# PowerStack.net
KiCad netlist of a schematic drawn in EasyEDA Pro
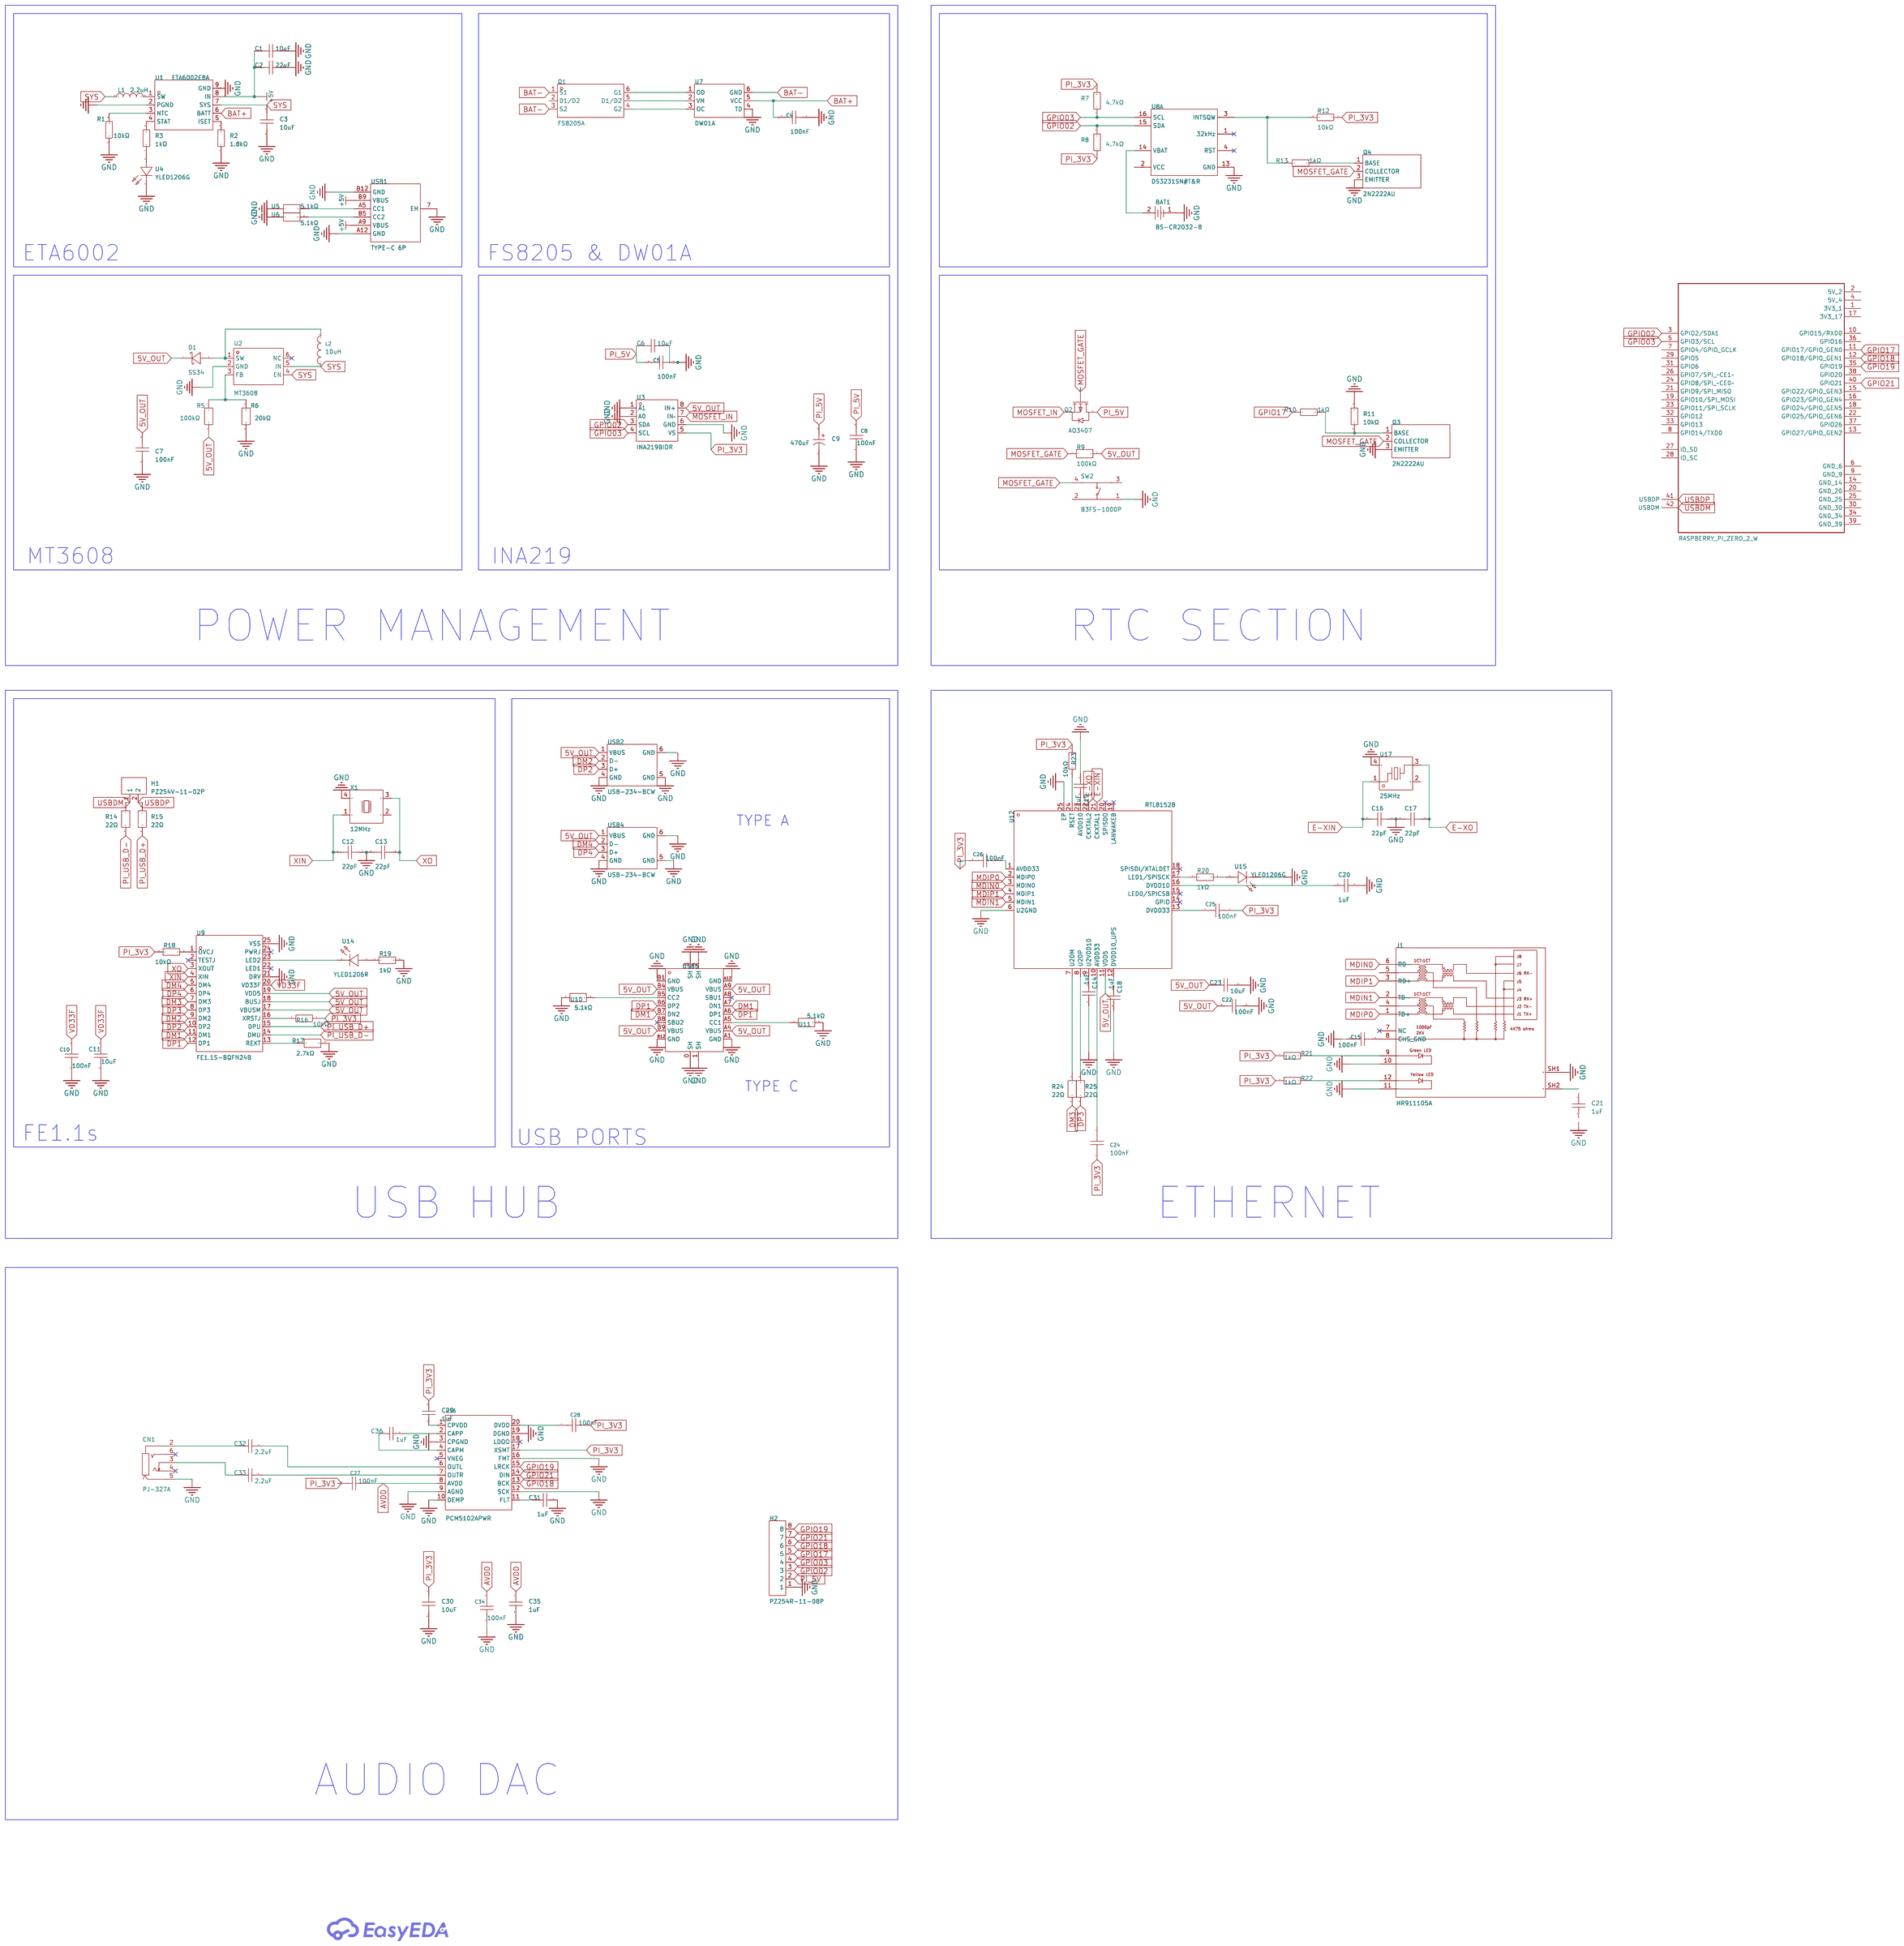
[diagram p0: schematic sheet]

(export (version "E")
  (design (tool "Eeschema 10.0.6"))
  (components
    (comp (ref "BAT1")
      (value "BS-CR2032-8")
      (footprint "easyedapro:BAT-SMD_BS-CR2032-8")
      (fields (field (name "Manufacturer") "LX(连欣科技)"))
      (libsource (lib "easyedapro") (part "BS-CR2032-8"))
    )
    (comp (ref "C1")
      (value "10uF")
      (footprint "easyedapro:C0603")
      (description "Capacitance:10uF Tolerance:±10% Tolerance:±10% Voltage Rating:10V Temperature Coefficient:X5R")
      (fields
        (field (name "Manufacturer Part") "CL10A106KP8NNNC")
        (field (name "Manufacturer") "SAMSUNG(三星)")
      )
      (libsource (lib "easyedapro") (part "CL10A106KP8NNNC"))
    )
    (comp (ref "C2")
      (value "22uF")
      (footprint "easyedapro:C0603")
      (description "Capacitance:22uF Tolerance:±20% Tolerance:±20% Voltage Rating:10V Temperature Coefficient:X5R")
      (fields
        (field (name "Manufacturer Part") "CL10A226MP8NUNE")
        (field (name "Manufacturer") "SAMSUNG(三星)")
      )
      (libsource (lib "easyedapro") (part "CL10A226MP8NUNE"))
    )
    (comp (ref "C3")
      (value "10uF")
      (footprint "easyedapro:C0603")
      (description "Capacitance:10uF Tolerance:±10% Tolerance:±10% Voltage Rating:10V Temperature Coefficient:X5R")
      (fields
        (field (name "Manufacturer Part") "CL10A106KP8NNNC")
        (field (name "Manufacturer") "SAMSUNG(三星)")
      )
      (libsource (lib "easyedapro") (part "CL10A106KP8NNNC"))
    )
    (comp (ref "C4")
      (value "100nF")
      (footprint "easyedapro:C0603")
      (description "Capacitance:100nF Tolerance:±10% Tolerance:±10% Voltage Rating:50V Temperature Coefficient:X7R")
      (fields
        (field (name "Manufacturer Part") "CC0603KRX7R9BB104")
        (field (name "Manufacturer") "YAGEO(国巨)")
      )
      (libsource (lib "easyedapro") (part "CC0603KRX7R9BB104"))
    )
    (comp (ref "C5")
      (value "100nF")
      (footprint "easyedapro:C0603")
      (description "Capacitance:100nF Tolerance:±10% Tolerance:±10% Voltage Rating:50V Temperature Coefficient:X7R")
      (fields
        (field (name "Manufacturer Part") "CC0603KRX7R9BB104")
        (field (name "Manufacturer") "YAGEO(国巨)")
      )
      (libsource (lib "easyedapro") (part "CC0603KRX7R9BB104"))
    )
    (comp (ref "C6")
      (value "10uF")
      (footprint "easyedapro:C0603")
      (description "Capacitance:10uF Tolerance:±10% Tolerance:±10% Voltage Rating:10V Temperature Coefficient:X5R")
      (fields
        (field (name "Manufacturer Part") "CL10A106KP8NNNC")
        (field (name "Manufacturer") "SAMSUNG(三星)")
      )
      (libsource (lib "easyedapro") (part "CL10A106KP8NNNC"))
    )
    (comp (ref "C7")
      (value "100nF")
      (footprint "easyedapro:C0603")
      (description "Capacitance:100nF Tolerance:±10% Tolerance:±10% Voltage Rating:50V Temperature Coefficient:X7R")
      (fields
        (field (name "Manufacturer Part") "CC0603KRX7R9BB104")
        (field (name "Manufacturer") "YAGEO(国巨)")
      )
      (libsource (lib "easyedapro") (part "CC0603KRX7R9BB104"))
    )
    (comp (ref "C8")
      (value "100nF")
      (footprint "easyedapro:C0603")
      (description "Capacitance:100nF Tolerance:±10% Tolerance:±10% Voltage Rating:50V Temperature Coefficient:X7R")
      (fields
        (field (name "Manufacturer Part") "CC0603KRX7R9BB104")
        (field (name "Manufacturer") "YAGEO(国巨)")
      )
      (libsource (lib "easyedapro") (part "CC0603KRX7R9BB104"))
    )
    (comp (ref "C9")
      (value "470uF")
      (footprint "easyedapro:CAP-SMD_BD6.3-L6.6-W6.6-FD")
      (fields (field (name "Manufacturer Part") "126RV0010") (field (name "Manufacturer") "KNSCHA(科尼盛)"))
      (libsource (lib "easyedapro") (part "126RV0010"))
    )
    (comp (ref "C10")
      (value "100nF")
      (footprint "easyedapro:C0603")
      (description "Capacitance:100nF Tolerance:±10% Tolerance:±10% Voltage Rating:50V Temperature Coefficient:X7R")
      (fields
        (field (name "Manufacturer Part") "CC0603KRX7R9BB104")
        (field (name "Manufacturer") "YAGEO(国巨)")
      )
      (libsource (lib "easyedapro") (part "CC0603KRX7R9BB104"))
    )
    (comp (ref "C11")
      (value "10uF")
      (footprint "easyedapro:C0603")
      (description "Capacitance:10uF Tolerance:±10% Tolerance:±10% Voltage Rating:10V Temperature Coefficient:X5R")
      (fields
        (field (name "Manufacturer Part") "CL10A106KP8NNNC")
        (field (name "Manufacturer") "SAMSUNG(三星)")
      )
      (libsource (lib "easyedapro") (part "CL10A106KP8NNNC"))
    )
    (comp (ref "C12")
      (value "22pF")
      (footprint "easyedapro:C0805")
      (description "Capacitance:22pF Tolerance:±5% Tolerance:±5% Voltage Rating:50V Temperature Coefficient:C0G")
      (fields
        (field (name "Manufacturer Part") "TCC0805COG220J500BT")
        (field (name "Manufacturer") "CCTC(三环)")
      )
      (libsource (lib "easyedapro") (part "TCC0805COG220J500BT"))
    )
    (comp (ref "C13")
      (value "22pF")
      (footprint "easyedapro:C0805")
      (description "Capacitance:22pF Tolerance:±5% Tolerance:±5% Voltage Rating:50V Temperature Coefficient:C0G")
      (fields
        (field (name "Manufacturer Part") "TCC0805COG220J500BT")
        (field (name "Manufacturer") "CCTC(三环)")
      )
      (libsource (lib "easyedapro") (part "TCC0805COG220J500BT"))
    )
    (comp (ref "C14")
      (value "1uF")
      (footprint "easyedapro:C0603")
      (description "Capacitance:1uF Tolerance:±10% Tolerance:±10% Voltage Rating:25V Temperature Coefficient:X7R")
      (fields
        (field (name "Manufacturer Part") "CL10B105KA8NNNC")
        (field (name "Manufacturer") "SAMSUNG(三星)")
      )
      (libsource (lib "easyedapro") (part "CL10B105KA8NNNC"))
    )
    (comp (ref "C15")
      (value "100nF")
      (footprint "easyedapro:C0603")
      (description "Capacitance:100nF Tolerance:±10% Tolerance:±10% Voltage Rating:50V Temperature Coefficient:X7R")
      (fields
        (field (name "Manufacturer Part") "CC0603KRX7R9BB104")
        (field (name "Manufacturer") "YAGEO(国巨)")
      )
      (libsource (lib "easyedapro") (part "CC0603KRX7R9BB104"))
    )
    (comp (ref "C16")
      (value "22pF")
      (footprint "easyedapro:C0805")
      (description "Capacitance:22pF Tolerance:±5% Tolerance:±5% Voltage Rating:50V Temperature Coefficient:C0G")
      (fields
        (field (name "Manufacturer Part") "TCC0805COG220J500BT")
        (field (name "Manufacturer") "CCTC(三环)")
      )
      (libsource (lib "easyedapro") (part "TCC0805COG220J500BT"))
    )
    (comp (ref "C17")
      (value "22pF")
      (footprint "easyedapro:C0805")
      (description "Capacitance:22pF Tolerance:±5% Tolerance:±5% Voltage Rating:50V Temperature Coefficient:C0G")
      (fields
        (field (name "Manufacturer Part") "TCC0805COG220J500BT")
        (field (name "Manufacturer") "CCTC(三环)")
      )
      (libsource (lib "easyedapro") (part "TCC0805COG220J500BT"))
    )
    (comp (ref "C18")
      (value "1uF")
      (footprint "easyedapro:C0603")
      (description "Capacitance:1uF Tolerance:±10% Tolerance:±10% Voltage Rating:25V Temperature Coefficient:X7R")
      (fields
        (field (name "Manufacturer Part") "CL10B105KA8NNNC")
        (field (name "Manufacturer") "SAMSUNG(三星)")
      )
      (libsource (lib "easyedapro") (part "CL10B105KA8NNNC"))
    )
    (comp (ref "C19")
      (value "1uF")
      (footprint "easyedapro:C0603")
      (description "Capacitance:1uF Tolerance:±10% Tolerance:±10% Voltage Rating:25V Temperature Coefficient:X7R")
      (fields
        (field (name "Manufacturer Part") "CL10B105KA8NNNC")
        (field (name "Manufacturer") "SAMSUNG(三星)")
      )
      (libsource (lib "easyedapro") (part "CL10B105KA8NNNC"))
    )
    (comp (ref "C20")
      (value "1uF")
      (footprint "easyedapro:C0603")
      (description "Capacitance:1uF Tolerance:±10% Tolerance:±10% Voltage Rating:25V Temperature Coefficient:X7R")
      (fields
        (field (name "Manufacturer Part") "CL10B105KA8NNNC")
        (field (name "Manufacturer") "SAMSUNG(三星)")
      )
      (libsource (lib "easyedapro") (part "CL10B105KA8NNNC"))
    )
    (comp (ref "C21")
      (value "1uF")
      (footprint "easyedapro:C0603")
      (description "Capacitance:1uF Tolerance:±10% Tolerance:±10% Voltage Rating:25V Temperature Coefficient:X7R")
      (fields
        (field (name "Manufacturer Part") "CL10B105KA8NNNC")
        (field (name "Manufacturer") "SAMSUNG(三星)")
      )
      (libsource (lib "easyedapro") (part "CL10B105KA8NNNC"))
    )
    (comp (ref "C22")
      (value "100nF")
      (footprint "easyedapro:C0603")
      (description "Capacitance:100nF Tolerance:±10% Tolerance:±10% Voltage Rating:50V Temperature Coefficient:X7R")
      (fields
        (field (name "Manufacturer Part") "CC0603KRX7R9BB104")
        (field (name "Manufacturer") "YAGEO(国巨)")
      )
      (libsource (lib "easyedapro") (part "CC0603KRX7R9BB104"))
    )
    (comp (ref "C23")
      (value "10uF")
      (footprint "easyedapro:C0603")
      (description "Capacitance:10uF Tolerance:±10% Tolerance:±10% Voltage Rating:10V Temperature Coefficient:X5R")
      (fields
        (field (name "Manufacturer Part") "CL10A106KP8NNNC")
        (field (name "Manufacturer") "SAMSUNG(三星)")
      )
      (libsource (lib "easyedapro") (part "CL10A106KP8NNNC"))
    )
    (comp (ref "C24")
      (value "100nF")
      (footprint "easyedapro:C0603")
      (description "Capacitance:100nF Tolerance:±10% Tolerance:±10% Voltage Rating:50V Temperature Coefficient:X7R")
      (fields
        (field (name "Manufacturer Part") "CC0603KRX7R9BB104")
        (field (name "Manufacturer") "YAGEO(国巨)")
      )
      (libsource (lib "easyedapro") (part "CC0603KRX7R9BB104"))
    )
    (comp (ref "C25")
      (value "100nF")
      (footprint "easyedapro:C0603")
      (description "Capacitance:100nF Tolerance:±10% Tolerance:±10% Voltage Rating:50V Temperature Coefficient:X7R")
      (fields
        (field (name "Manufacturer Part") "CC0603KRX7R9BB104")
        (field (name "Manufacturer") "YAGEO(国巨)")
      )
      (libsource (lib "easyedapro") (part "CC0603KRX7R9BB104"))
    )
    (comp (ref "C26")
      (value "100nF")
      (footprint "easyedapro:C0603")
      (description "Capacitance:100nF Tolerance:±10% Tolerance:±10% Voltage Rating:50V Temperature Coefficient:X7R")
      (fields
        (field (name "Manufacturer Part") "CC0603KRX7R9BB104")
        (field (name "Manufacturer") "YAGEO(国巨)")
      )
      (libsource (lib "easyedapro") (part "CC0603KRX7R9BB104"))
    )
    (comp (ref "C27")
      (value "100nF")
      (footprint "easyedapro:C0603")
      (description "Capacitance:100nF Tolerance:±10% Tolerance:±10% Voltage Rating:50V Temperature Coefficient:X7R")
      (fields
        (field (name "Manufacturer Part") "CC0603KRX7R9BB104")
        (field (name "Manufacturer") "YAGEO(国巨)")
      )
      (libsource (lib "easyedapro") (part "CC0603KRX7R9BB104"))
    )
    (comp (ref "C28")
      (value "100nF")
      (footprint "easyedapro:C0603")
      (description "Capacitance:100nF Tolerance:±10% Tolerance:±10% Voltage Rating:50V Temperature Coefficient:X7R")
      (fields
        (field (name "Manufacturer Part") "CC0603KRX7R9BB104")
        (field (name "Manufacturer") "YAGEO(国巨)")
      )
      (libsource (lib "easyedapro") (part "CC0603KRX7R9BB104"))
    )
    (comp (ref "C29")
      (value "1uF")
      (footprint "easyedapro:C0603")
      (description "Capacitance:1uF Tolerance:±10% Tolerance:±10% Voltage Rating:25V Temperature Coefficient:X7R")
      (fields
        (field (name "Manufacturer Part") "CL10B105KA8NNNC")
        (field (name "Manufacturer") "SAMSUNG(三星)")
      )
      (libsource (lib "easyedapro") (part "CL10B105KA8NNNC"))
    )
    (comp (ref "C30")
      (value "10uF")
      (footprint "easyedapro:C0603")
      (description "Capacitance:10uF Tolerance:±10% Tolerance:±10% Voltage Rating:10V Temperature Coefficient:X5R")
      (fields
        (field (name "Manufacturer Part") "CL10A106KP8NNNC")
        (field (name "Manufacturer") "SAMSUNG(三星)")
      )
      (libsource (lib "easyedapro") (part "CL10A106KP8NNNC"))
    )
    (comp (ref "C31")
      (value "1uF")
      (footprint "easyedapro:C0603")
      (description "Capacitance:1uF Tolerance:±10% Tolerance:±10% Voltage Rating:25V Temperature Coefficient:X7R")
      (fields
        (field (name "Manufacturer Part") "CL10B105KA8NNNC")
        (field (name "Manufacturer") "SAMSUNG(三星)")
      )
      (libsource (lib "easyedapro") (part "CL10B105KA8NNNC"))
    )
    (comp (ref "C32")
      (value "2.2uF")
      (footprint "easyedapro:C0603")
      (description "Capacitance:2.2uF Tolerance:±10% Tolerance:±10% Voltage Rating:16V Temperature Coefficient:X5R")
      (fields
        (field (name "Manufacturer Part") "CL10A225KO8NNNC")
        (field (name "Manufacturer") "SAMSUNG(三星)")
      )
      (libsource (lib "easyedapro") (part "CL10A225KO8NNNC"))
    )
    (comp (ref "C33")
      (value "2.2uF")
      (footprint "easyedapro:C0603")
      (description "Capacitance:2.2uF Tolerance:±10% Tolerance:±10% Voltage Rating:16V Temperature Coefficient:X5R")
      (fields
        (field (name "Manufacturer Part") "CL10A225KO8NNNC")
        (field (name "Manufacturer") "SAMSUNG(三星)")
      )
      (libsource (lib "easyedapro") (part "CL10A225KO8NNNC"))
    )
    (comp (ref "C34")
      (value "100nF")
      (footprint "easyedapro:C0603")
      (description "Capacitance:100nF Tolerance:±10% Tolerance:±10% Voltage Rating:50V Temperature Coefficient:X7R")
      (fields
        (field (name "Manufacturer Part") "CC0603KRX7R9BB104")
        (field (name "Manufacturer") "YAGEO(国巨)")
      )
      (libsource (lib "easyedapro") (part "CC0603KRX7R9BB104"))
    )
    (comp (ref "C35")
      (value "1uF")
      (footprint "easyedapro:C0603")
      (description "Capacitance:1uF Tolerance:±10% Tolerance:±10% Voltage Rating:25V Temperature Coefficient:X7R")
      (fields
        (field (name "Manufacturer Part") "CL10B105KA8NNNC")
        (field (name "Manufacturer") "SAMSUNG(三星)")
      )
      (libsource (lib "easyedapro") (part "CL10B105KA8NNNC"))
    )
    (comp (ref "C36")
      (value "1uF")
      (footprint "easyedapro:C0603")
      (description "Capacitance:1uF Tolerance:±10% Tolerance:±10% Voltage Rating:25V Temperature Coefficient:X7R")
      (fields
        (field (name "Manufacturer Part") "CL10B105KA8NNNC")
        (field (name "Manufacturer") "SAMSUNG(三星)")
      )
      (libsource (lib "easyedapro") (part "CL10B105KA8NNNC"))
    )
    (comp (ref "CN1")
      (value "PJ-327A")
      (footprint "easyedapro:AUDIO-SMD_XUNPU_PJ-327A")
      (fields (field (name "Manufacturer") "XUNPU(讯普)"))
      (libsource (lib "easyedapro") (part "PJ-327A"))
    )
    (comp (ref "D1")
      (value "SS34")
      (footprint "easyedapro:SMA_L4.3-W2.6-LS5.1-RD")
      (fields (field (name "Manufacturer") "Hangyu(航昱微)"))
      (libsource (lib "easyedapro") (part "SS34_C52023881"))
    )
    (comp (ref "H1")
      (value "PZ254V-11-02P")
      (footprint "easyedapro:HDR-TH_2P-P2.54-V-M")
      (fields (field (name "Manufacturer") "XFCN(兴飞)"))
      (libsource (lib "easyedapro") (part "PZ254V-11-02P"))
    )
    (comp (ref "H2")
      (value "PZ254R-11-08P")
      (footprint "easyedapro:HDR-TH_8P-P2.54-H-M-W10.4")
      (fields (field (name "Manufacturer") "XFCN(兴飞)"))
      (libsource (lib "easyedapro") (part "PZ254R-11-08P"))
    )
    (comp (ref "J1")
      (value "HR911105A")
      (footprint "easyedapro:RJ45-TH_HR911105A")
      (fields (field (name "Manufacturer") "HANRUN(汉仁)"))
      (libsource (lib "easyedapro") (part "HR911105A_C12074"))
    )
    (comp (ref "L1")
      (value "2.2uH")
      (footprint "easyedapro:IND-SMD_L5.4-W5.2")
      (fields (field (name "Manufacturer Part") "APH0530T2R2M") (field (name "Manufacturer") "APV(爱普微)"))
      (libsource (lib "easyedapro") (part "APH0530T2R2M"))
    )
    (comp (ref "L2")
      (value "10uH")
      (footprint "easyedapro:IND-SMD_L5.2-W5.2_MCW-0530")
      (fields (field (name "Manufacturer Part") "SMMS0530-100M") (field (name "Manufacturer") "SXN(顺翔诺)"))
      (libsource (lib "easyedapro") (part "SMMS0530-100M"))
    )
    (comp (ref "Q1")
      (value "FS8205A")
      (footprint "easyedapro:SOT-23-6_L2.9-W1.6-P0.95-LS2.8-BR")
      (fields (field (name "Manufacturer") "TECH PUBLIC(台舟)"))
      (libsource (lib "easyedapro") (part "FS8205A_C2830320"))
    )
    (comp (ref "Q2")
      (value "AO3407")
      (footprint "easyedapro:SOT-23-3_L2.9-W1.6-P1.90-LS2.8-BR")
      (fields (field (name "Manufacturer") "YONGYUTAI(永裕泰)"))
      (libsource (lib "easyedapro") (part "AO3407_C54839874"))
    )
    (comp (ref "Q3")
      (value "2N2222AU")
      (footprint "easyedapro:SOT-89-3_L4.5-W2.4-P1.50-LS4.0-BR")
      (fields (field (name "Manufacturer") "CBI(创基)"))
      (libsource (lib "easyedapro") (part "2N2222AU"))
    )
    (comp (ref "Q4")
      (value "2N2222AU")
      (footprint "easyedapro:SOT-89-3_L4.5-W2.4-P1.50-LS4.0-BR")
      (fields (field (name "Manufacturer") "CBI(创基)"))
      (libsource (lib "easyedapro") (part "2N2222AU"))
    )
    (comp (ref "R1")
      (value "10kΩ")
      (footprint "easyedapro:R0603")
      (fields (field (name "Manufacturer Part") "RC0603FR-0710KL") (field (name "Manufacturer") "YAGEO(国巨)"))
      (libsource (lib "easyedapro") (part "RC0603FR-0710KL"))
    )
    (comp (ref "R2")
      (value "1.8kΩ")
      (footprint "easyedapro:R0603")
      (fields (field (name "Manufacturer Part") "RC0603FR-071K8L") (field (name "Manufacturer") "YAGEO(国巨)"))
      (libsource (lib "easyedapro") (part "RC0603FR-071K8L"))
    )
    (comp (ref "R3")
      (value "1kΩ")
      (footprint "easyedapro:R0603")
      (fields (field (name "Manufacturer Part") "RC0603FR-071KL") (field (name "Manufacturer") "YAGEO(国巨)"))
      (libsource (lib "easyedapro") (part "RC0603FR-071KL"))
    )
    (comp (ref "R5")
      (value "100kΩ")
      (footprint "easyedapro:R0603")
      (fields (field (name "Manufacturer Part") "FRC0603F1003TS") (field (name "Manufacturer") "FOJAN(富捷)"))
      (libsource (lib "easyedapro") (part "FRC0603F1003TS"))
    )
    (comp (ref "R6")
      (value "20kΩ")
      (footprint "easyedapro:R0603")
      (fields (field (name "Manufacturer Part") "FRC0603F2002TS") (field (name "Manufacturer") "FOJAN(富捷)"))
      (libsource (lib "easyedapro") (part "FRC0603F2002TS"))
    )
    (comp (ref "R7")
      (value "4.7kΩ")
      (footprint "easyedapro:R0603")
      (fields (field (name "Manufacturer Part") "RC0603FR-074K7L") (field (name "Manufacturer") "YAGEO(国巨)"))
      (libsource (lib "easyedapro") (part "RC0603FR-074K7L"))
    )
    (comp (ref "R8")
      (value "4.7kΩ")
      (footprint "easyedapro:R0603")
      (fields (field (name "Manufacturer Part") "RC0603FR-074K7L") (field (name "Manufacturer") "YAGEO(国巨)"))
      (libsource (lib "easyedapro") (part "RC0603FR-074K7L"))
    )
    (comp (ref "R9")
      (value "100kΩ")
      (footprint "easyedapro:R0603")
      (fields (field (name "Manufacturer Part") "FRC0603F1003TS") (field (name "Manufacturer") "FOJAN(富捷)"))
      (libsource (lib "easyedapro") (part "FRC0603F1003TS"))
    )
    (comp (ref "R10")
      (value "1kΩ")
      (footprint "easyedapro:R0603")
      (fields (field (name "Manufacturer Part") "RC0603FR-071KL") (field (name "Manufacturer") "YAGEO(国巨)"))
      (libsource (lib "easyedapro") (part "RC0603FR-071KL"))
    )
    (comp (ref "R11")
      (value "10kΩ")
      (footprint "easyedapro:R0603")
      (fields (field (name "Manufacturer Part") "RC0603FR-0710KL") (field (name "Manufacturer") "YAGEO(国巨)"))
      (libsource (lib "easyedapro") (part "RC0603FR-0710KL"))
    )
    (comp (ref "R12")
      (value "10kΩ")
      (footprint "easyedapro:R0603")
      (fields (field (name "Manufacturer Part") "RC0603FR-0710KL") (field (name "Manufacturer") "YAGEO(国巨)"))
      (libsource (lib "easyedapro") (part "RC0603FR-0710KL"))
    )
    (comp (ref "R13")
      (value "1kΩ")
      (footprint "easyedapro:R0603")
      (fields (field (name "Manufacturer Part") "RC0603FR-071KL") (field (name "Manufacturer") "YAGEO(国巨)"))
      (libsource (lib "easyedapro") (part "RC0603FR-071KL"))
    )
    (comp (ref "R14")
      (value "22Ω")
      (footprint "easyedapro:R0603")
      (fields (field (name "Manufacturer Part") "FRC0603F22R0TS") (field (name "Manufacturer") "FOJAN(富捷)"))
      (libsource (lib "easyedapro") (part "FRC0603F22R0TS"))
    )
    (comp (ref "R15")
      (value "22Ω")
      (footprint "easyedapro:R0603")
      (fields (field (name "Manufacturer Part") "FRC0603F22R0TS") (field (name "Manufacturer") "FOJAN(富捷)"))
      (libsource (lib "easyedapro") (part "FRC0603F22R0TS"))
    )
    (comp (ref "R16")
      (value "10kΩ")
      (footprint "easyedapro:R0603")
      (fields (field (name "Manufacturer Part") "RC0603FR-0710KL") (field (name "Manufacturer") "YAGEO(国巨)"))
      (libsource (lib "easyedapro") (part "RC0603FR-0710KL"))
    )
    (comp (ref "R17")
      (value "2.7kΩ")
      (footprint "easyedapro:R0603")
      (fields (field (name "Manufacturer Part") "FRC0603F2701TS") (field (name "Manufacturer") "FOJAN(富捷)"))
      (libsource (lib "easyedapro") (part "FRC0603F2701TS"))
    )
    (comp (ref "R18")
      (value "10kΩ")
      (footprint "easyedapro:R0603")
      (fields (field (name "Manufacturer Part") "RC0603FR-0710KL") (field (name "Manufacturer") "YAGEO(国巨)"))
      (libsource (lib "easyedapro") (part "RC0603FR-0710KL"))
    )
    (comp (ref "R19")
      (value "1kΩ")
      (footprint "easyedapro:R0603")
      (fields (field (name "Manufacturer Part") "RC0603FR-071KL") (field (name "Manufacturer") "YAGEO(国巨)"))
      (libsource (lib "easyedapro") (part "RC0603FR-071KL"))
    )
    (comp (ref "R20")
      (value "1kΩ")
      (footprint "easyedapro:R0603")
      (fields (field (name "Manufacturer Part") "RC0603FR-071KL") (field (name "Manufacturer") "YAGEO(国巨)"))
      (libsource (lib "easyedapro") (part "RC0603FR-071KL"))
    )
    (comp (ref "R21")
      (value "1kΩ")
      (footprint "easyedapro:R0603")
      (fields (field (name "Manufacturer Part") "RC0603FR-071KL") (field (name "Manufacturer") "YAGEO(国巨)"))
      (libsource (lib "easyedapro") (part "RC0603FR-071KL"))
    )
    (comp (ref "R22")
      (value "1kΩ")
      (footprint "easyedapro:R0603")
      (fields (field (name "Manufacturer Part") "RC0603FR-071KL") (field (name "Manufacturer") "YAGEO(国巨)"))
      (libsource (lib "easyedapro") (part "RC0603FR-071KL"))
    )
    (comp (ref "R23")
      (value "10kΩ")
      (footprint "easyedapro:R0603")
      (fields (field (name "Manufacturer Part") "RC0603FR-0710KL") (field (name "Manufacturer") "YAGEO(国巨)"))
      (libsource (lib "easyedapro") (part "RC0603FR-0710KL"))
    )
    (comp (ref "R24")
      (value "22Ω")
      (footprint "easyedapro:R0603")
      (fields (field (name "Manufacturer Part") "FRC0603F22R0TS") (field (name "Manufacturer") "FOJAN(富捷)"))
      (libsource (lib "easyedapro") (part "FRC0603F22R0TS"))
    )
    (comp (ref "R25")
      (value "22Ω")
      (footprint "easyedapro:R0603")
      (fields (field (name "Manufacturer Part") "FRC0603F22R0TS") (field (name "Manufacturer") "FOJAN(富捷)"))
      (libsource (lib "easyedapro") (part "FRC0603F22R0TS"))
    )
    (comp (ref "SW2")
      (value "B3FS-1000P")
      (footprint "easyedapro:KEY-SMD_4P-L6.0-W6.3-P4.50-LS8.0")
      (fields (field (name "Manufacturer") "OMRON(欧姆龙)"))
      (libsource (lib "easyedapro") (part "B3FS-1000P"))
    )
    (comp (ref "U1")
      (value "ETA6002E8A")
      (footprint "easyedapro:ESOP-8_L4.9-W3.9-P1.27-LS6.0-BL-EP-1")
      (fields (field (name "Manufacturer") "ETA(钰泰)"))
      (libsource (lib "easyedapro") (part "ETA6002E8A"))
    )
    (comp (ref "U2")
      (value "MT3608")
      (footprint "easyedapro:SOT-23-6_L2.9-W1.6-P0.95-LS2.8-BL")
      (fields (field (name "Manufacturer") "西安航天民芯"))
      (libsource (lib "easyedapro") (part "MT3608"))
    )
    (comp (ref "U3")
      (value "INA219BIDR")
      (footprint "easyedapro:SOIC-8_L5.0-W4.0-P1.27-LS6.1-BL")
      (fields (field (name "Manufacturer") "TI(德州仪器)"))
      (libsource (lib "easyedapro") (part "INA219BIDR"))
    )
    (comp (ref "U4")
      (value "YLED1206G")
      (footprint "easyedapro:LED1206-RD")
      (fields (field (name "Manufacturer") "YONGYUTAI(永裕泰)"))
      (libsource (lib "easyedapro") (part "YLED1206G"))
    )
    (comp (ref "U5")
      (value "5.1kΩ")
      (footprint "easyedapro:R0603")
      (fields (field (name "Manufacturer Part") "FRC0603F5101TS") (field (name "Manufacturer") "FOJAN(富捷)"))
      (libsource (lib "easyedapro") (part "FRC0603F5101TS"))
    )
    (comp (ref "U6")
      (value "5.1kΩ")
      (footprint "easyedapro:R0603")
      (fields (field (name "Manufacturer Part") "FRC0603F5101TS") (field (name "Manufacturer") "FOJAN(富捷)"))
      (libsource (lib "easyedapro") (part "FRC0603F5101TS"))
    )
    (comp (ref "U7")
      (value "DW01A")
      (footprint "easyedapro:SOT-23-6_L2.9-W1.6-P0.95-LS2.8-BL")
      (fields (field (name "Manufacturer") "PUOLOP(迪浦)"))
      (libsource (lib "easyedapro") (part "DW01A_C351410"))
    )
    (comp (ref "U8")
      (value "DS3231SN#T&R")
      (footprint "easyedapro:SOIC-16_L10.3-W7.5-P1.27-LS10.3-BL")
      (fields (field (name "Manufacturer") "ADI(亚德诺)/MAXIM(美信)"))
      (libsource (lib "easyedapro") (part "DS3231SN#"))
    )
    (comp (ref "U9")
      (value "FE1.1S-BQFN24B")
      (footprint "easyedapro:WQFN-24_L4.0-W4.0-P0.50-TL-EP2.7")
      (fields (field (name "Manufacturer") "TERMINUS"))
      (libsource (lib "easyedapro") (part "FE1.1S-BQFN24B"))
    )
    (comp (ref "U10")
      (value "5.1kΩ")
      (footprint "easyedapro:R0603")
      (fields (field (name "Manufacturer Part") "FRC0603F5101TS") (field (name "Manufacturer") "FOJAN(富捷)"))
      (libsource (lib "easyedapro") (part "FRC0603F5101TS"))
    )
    (comp (ref "U11")
      (value "5.1kΩ")
      (footprint "easyedapro:R0603")
      (fields (field (name "Manufacturer Part") "FRC0603F5101TS") (field (name "Manufacturer") "FOJAN(富捷)"))
      (libsource (lib "easyedapro") (part "FRC0603F5101TS"))
    )
    (comp (ref "U12")
      (value "RTL8152B")
      (footprint "easyedapro:QFN-24_L4.0-W4.0-P0.50-BL-EP2.0")
      (fields (field (name "Manufacturer") "REALTEK(瑞昱)"))
      (libsource (lib "easyedapro") (part "RTL8152B-VB-CG"))
    )
    (comp (ref "U14")
      (value "YLED1206R")
      (footprint "easyedapro:LED1206-FD")
      (fields (field (name "Manufacturer") "YONGYUTAI(永裕泰)"))
      (libsource (lib "easyedapro") (part "YLED1206R"))
    )
    (comp (ref "U15")
      (value "YLED1206G")
      (footprint "easyedapro:LED1206-RD")
      (fields (field (name "Manufacturer") "YONGYUTAI(永裕泰)"))
      (libsource (lib "easyedapro") (part "YLED1206G"))
    )
    (comp (ref "U16")
      (value "PCM5102APWR")
      (footprint "easyedapro:TSSOP-20_L6.5-W4.4-P0.65-LS6.4-BL")
      (fields (field (name "Manufacturer") "TI(德州仪器)"))
      (libsource (lib "easyedapro") (part "PCM5102APWR"))
    )
    (comp (ref "U17")
      (value "25MHz")
      (footprint "easyedapro:CRYSTAL-SMD_4P-L2.0-W1.6-BL")
      (fields
        (field (name "Manufacturer Part") "XL7EL89CKI-111YLC-25M")
        (field (name "Manufacturer") "YXC(扬兴晶振)")
      )
      (libsource (lib "easyedapro") (part "XL7EL89CKI-111YLC-25M"))
    )
    (comp (ref "U18")
      (value "RASPBERRY_PI_ZERO_2_W")
      (footprint "easyedapro:MODULE_RASPBERRY_PI_ZERO_2_W")
      (libsource (lib "easyedapro") (part "RASPBERRY_PI_ZERO_2_W"))
    )
    (comp (ref "USB1")
      (value "TYPE-C 6P")
      (footprint "easyedapro:TYPE-C-SMD_TYPE-C-6P_1")
      (fields (field (name "Manufacturer") "SHOU HAN(首韩)"))
      (libsource (lib "easyedapro") (part "TYPE-C 6P"))
    )
    (comp (ref "USB2")
      (value "USB-234-BCW")
      (footprint "easyedapro:USB-A-SMD_USB-234-BCW")
      (fields (field (name "Manufacturer") "XUNPU(讯普)"))
      (libsource (lib "easyedapro") (part "USB-234-BCW"))
    )
    (comp (ref "USB4")
      (value "USB-234-BCW")
      (footprint "easyedapro:USB-A-SMD_USB-234-BCW")
      (fields (field (name "Manufacturer") "XUNPU(讯普)"))
      (libsource (lib "easyedapro") (part "USB-234-BCW"))
    )
    (comp (ref "USB5")
      (value "TYPE C")
      (footprint "easyedapro:USB-C_SMD-TYPE-C-31-M-12")
      (fields (field (name "Manufacturer") "DEALON(德艺隆)"))
      (libsource (lib "easyedapro") (part "USB-TYPE-C-018"))
    )
    (comp (ref "X1")
      (value "12MHz")
      (footprint "easyedapro:OSC-SMD_4P-L5.0-W3.2-BL_SG5032")
      (fields
        (field (name "Manufacturer Part") "OVETGLJANF-12MHZ")
        (field (name "Manufacturer") "TAITIEN(泰艺电子)")
      )
      (libsource (lib "easyedapro") (part "OVETGLJANF-12MHZ"))
    )
  )
  (nets
    (net (code "1") (name "+5V") (class "Default")
      (node (ref "C1") (pin "1") (pinfunction "1_1") (pintype "unspecified"))
      (node (ref "C2") (pin "1") (pinfunction "1_1") (pintype "unspecified"))
      (node (ref "U1") (pin "8") (pinfunction "IN_8") (pintype "unspecified"))
      (node (ref "USB1") (pin "A9") (pinfunction "VBUS_A9") (pintype "unspecified"))
      (node (ref "USB1") (pin "B9") (pinfunction "VBUS_B9") (pintype "unspecified"))
    )
    (net (code "2") (name "5V_OUT") (class "Default")
      (node (ref "C22") (pin "2") (pinfunction "2_2") (pintype "unspecified"))
      (node (ref "C23") (pin "1") (pinfunction "1_1") (pintype "unspecified"))
      (node (ref "C7") (pin "2") (pinfunction "2_2") (pintype "unspecified"))
      (node (ref "D1") (pin "1") (pinfunction "C_1") (pintype "unspecified"))
      (node (ref "R5") (pin "2") (pinfunction "2_2") (pintype "unspecified"))
      (node (ref "R9") (pin "2") (pinfunction "2_2") (pintype "unspecified"))
      (node (ref "U12") (pin "11") (pinfunction "VDD5_11") (pintype "unspecified"))
      (node (ref "U3") (pin "8") (pinfunction "IN+_8") (pintype "unspecified"))
      (node (ref "U9") (pin "17") (pinfunction "VBUSM_17") (pintype "unspecified"))
      (node (ref "U9") (pin "18") (pinfunction "BUSJ_18") (pintype "unspecified"))
      (node (ref "U9") (pin "19") (pinfunction "VDD5_19") (pintype "unspecified"))
      (node (ref "USB2") (pin "1") (pinfunction "VBUS_1") (pintype "unspecified"))
      (node (ref "USB4") (pin "1") (pinfunction "VBUS_1") (pintype "unspecified"))
      (node (ref "USB5") (pin "A4") (pinfunction "VBUS_A4") (pintype "unspecified"))
      (node (ref "USB5") (pin "A9") (pinfunction "VBUS_A9") (pintype "unspecified"))
      (node (ref "USB5") (pin "B4") (pinfunction "VBUS_B4") (pintype "unspecified"))
      (node (ref "USB5") (pin "B9") (pinfunction "VBUS_B9") (pintype "unspecified"))
    )
    (net (code "3") (name "AVDD") (class "Default")
      (node (ref "C27") (pin "1") (pinfunction "1_1") (pintype "unspecified"))
      (node (ref "C34") (pin "2") (pinfunction "2_2") (pintype "unspecified"))
      (node (ref "C35") (pin "1") (pinfunction "1_1") (pintype "input"))
      (node (ref "U16") (pin "8") (pinfunction "AVDD_8") (pintype "input"))
    )
    (net (code "4") (name "BAT+") (class "Default")
      (node (ref "C4") (pin "2") (pinfunction "2_2") (pintype "unspecified"))
      (node (ref "U1") (pin "6") (pinfunction "BATT_6") (pintype "unspecified"))
      (node (ref "U7") (pin "5") (pinfunction "VCC_5") (pintype "unspecified"))
    )
    (net (code "5") (name "BAT-") (class "Default")
      (node (ref "Q1") (pin "1") (pinfunction "S1_1") (pintype "unspecified"))
      (node (ref "Q1") (pin "3") (pinfunction "S2_3") (pintype "unspecified"))
      (node (ref "U7") (pin "6") (pinfunction "GND_6") (pintype "unspecified"))
    )
    (net (code "6") (name "DM1") (class "Default")
      (node (ref "U9") (pin "11") (pinfunction "DM1_11") (pintype "unspecified"))
      (node (ref "USB5") (pin "A7") (pinfunction "DN1_A7") (pintype "unspecified"))
      (node (ref "USB5") (pin "B7") (pinfunction "DN2_B7") (pintype "unspecified"))
    )
    (net (code "7") (name "DM2") (class "Default")
      (node (ref "U9") (pin "9") (pinfunction "DM2_9") (pintype "unspecified"))
      (node (ref "USB2") (pin "2") (pinfunction "D-_2") (pintype "unspecified"))
    )
    (net (code "8") (name "DM3") (class "Default")
      (node (ref "R24") (pin "2") (pinfunction "2_2") (pintype "unspecified"))
      (node (ref "U9") (pin "7") (pinfunction "DM3_7") (pintype "unspecified"))
    )
    (net (code "9") (name "DM4") (class "Default")
      (node (ref "U9") (pin "5") (pinfunction "DM4_5") (pintype "unspecified"))
      (node (ref "USB4") (pin "2") (pinfunction "D-_2") (pintype "unspecified"))
    )
    (net (code "10") (name "DP1") (class "Default")
      (node (ref "U9") (pin "12") (pinfunction "DP1_12") (pintype "unspecified"))
      (node (ref "USB5") (pin "A6") (pinfunction "DP1_A6") (pintype "unspecified"))
      (node (ref "USB5") (pin "B6") (pinfunction "DP2_B6") (pintype "unspecified"))
    )
    (net (code "11") (name "DP2") (class "Default")
      (node (ref "U9") (pin "10") (pinfunction "DP2_10") (pintype "unspecified"))
      (node (ref "USB2") (pin "3") (pinfunction "D+_3") (pintype "unspecified"))
    )
    (net (code "12") (name "DP3") (class "Default")
      (node (ref "R25") (pin "2") (pinfunction "2_2") (pintype "unspecified"))
      (node (ref "U9") (pin "8") (pinfunction "DP3_8") (pintype "unspecified"))
    )
    (net (code "13") (name "DP4") (class "Default")
      (node (ref "U9") (pin "6") (pinfunction "DP4_6") (pintype "unspecified"))
      (node (ref "USB4") (pin "3") (pinfunction "D+_3") (pintype "unspecified"))
    )
    (net (code "14") (name "E-XIN") (class "Default")
      (node (ref "C16") (pin "2") (pinfunction "2_2") (pintype "unspecified"))
      (node (ref "U12") (pin "21") (pinfunction "CKXTAL1_21") (pintype "unspecified"))
      (node (ref "U17") (pin "1") (pinfunction "1_1") (pintype "input"))
    )
    (net (code "15") (name "E-XO") (class "Default")
      (node (ref "C17") (pin "2") (pinfunction "2_2") (pintype "unspecified"))
      (node (ref "U12") (pin "22") (pinfunction "CKXTAL2_22") (pintype "unspecified"))
      (node (ref "U17") (pin "3") (pinfunction "3_3") (pintype "input"))
    )
    (net (code "16") (name "GND") (class "Default")
      (node (ref "BAT1") (pin "1") (pinfunction "1_1") (pintype "input"))
      (node (ref "C1") (pin "2") (pinfunction "2_2") (pintype "unspecified"))
      (node (ref "C10") (pin "1") (pinfunction "1_1") (pintype "unspecified"))
      (node (ref "C11") (pin "2") (pinfunction "2_2") (pintype "unspecified"))
      (node (ref "C12") (pin "1") (pinfunction "1_1") (pintype "unspecified"))
      (node (ref "C13") (pin "1") (pinfunction "1_1") (pintype "unspecified"))
      (node (ref "C14") (pin "1") (pinfunction "1_1") (pintype "input"))
      (node (ref "C15") (pin "2") (pinfunction "2_2") (pintype "unspecified"))
      (node (ref "C16") (pin "1") (pinfunction "1_1") (pintype "unspecified"))
      (node (ref "C17") (pin "1") (pinfunction "1_1") (pintype "unspecified"))
      (node (ref "C18") (pin "1") (pinfunction "1_1") (pintype "input"))
      (node (ref "C19") (pin "1") (pinfunction "1_1") (pintype "input"))
      (node (ref "C2") (pin "2") (pinfunction "2_2") (pintype "unspecified"))
      (node (ref "C20") (pin "1") (pinfunction "1_1") (pintype "input"))
      (node (ref "C22") (pin "1") (pinfunction "1_1") (pintype "unspecified"))
      (node (ref "C23") (pin "2") (pinfunction "2_2") (pintype "unspecified"))
      (node (ref "C3") (pin "2") (pinfunction "2_2") (pintype "unspecified"))
      (node (ref "C30") (pin "2") (pinfunction "2_2") (pintype "unspecified"))
      (node (ref "C31") (pin "2") (pinfunction "2_2") (pintype "input"))
      (node (ref "C34") (pin "1") (pinfunction "1_1") (pintype "unspecified"))
      (node (ref "C35") (pin "2") (pinfunction "2_2") (pintype "input"))
      (node (ref "C4") (pin "1") (pinfunction "1_1") (pintype "unspecified"))
      (node (ref "C5") (pin "1") (pinfunction "1_1") (pintype "unspecified"))
      (node (ref "C6") (pin "2") (pinfunction "2_2") (pintype "unspecified"))
      (node (ref "C7") (pin "1") (pinfunction "1_1") (pintype "unspecified"))
      (node (ref "C8") (pin "1") (pinfunction "1_1") (pintype "unspecified"))
      (node (ref "C9") (pin "2") (pinfunction "2_2") (pintype "input"))
      (node (ref "CN1") (pin "5") (pinfunction "5_5") (pintype "unspecified"))
      (node (ref "H2") (pin "1") (pinfunction "1_1") (pintype "unspecified"))
      (node (ref "J1") (pin "10") (pinfunction "10_10") (pintype "unspecified"))
      (node (ref "J1") (pin "11") (pinfunction "11_11") (pintype "unspecified"))
      (node (ref "J1") (pin "SH1") (pinfunction "SH1_SH1") (pintype "unspecified"))
      (node (ref "Q3") (pin "3") (pinfunction "EMITTER_3") (pintype "unspecified"))
      (node (ref "Q4") (pin "3") (pinfunction "EMITTER_3") (pintype "unspecified"))
      (node (ref "R1") (pin "1") (pinfunction "1_1") (pintype "input"))
      (node (ref "R11") (pin "1") (pinfunction "1_1") (pintype "input"))
      (node (ref "R17") (pin "2") (pinfunction "2_2") (pintype "unspecified"))
      (node (ref "R19") (pin "2") (pinfunction "2_2") (pintype "input"))
      (node (ref "R2") (pin "1") (pinfunction "1_1") (pintype "unspecified"))
      (node (ref "R6") (pin "1") (pinfunction "1_1") (pintype "unspecified"))
      (node (ref "SW2") (pin "1") (pinfunction "1_1") (pintype "unspecified"))
      (node (ref "U1") (pin "9") (pinfunction "GND_9") (pintype "unspecified"))
      (node (ref "U10") (pin "1") (pinfunction "1_1") (pintype "unspecified"))
      (node (ref "U11") (pin "2") (pinfunction "2_2") (pintype "unspecified"))
      (node (ref "U12") (pin "25") (pinfunction "EP_25") (pintype "unspecified"))
      (node (ref "U12") (pin "6") (pinfunction "U2GND_6") (pintype "unspecified"))
      (node (ref "U15") (pin "1") (pinfunction "K_1") (pintype "unspecified"))
      (node (ref "U16") (pin "10") (pinfunction "DEMP_10") (pintype "input"))
      (node (ref "U16") (pin "12") (pinfunction "SCK_12") (pintype "input"))
      (node (ref "U16") (pin "16") (pinfunction "FMT_16") (pintype "input"))
      (node (ref "U16") (pin "19") (pinfunction "DGND_19") (pintype "input"))
      (node (ref "U16") (pin "3") (pinfunction "CPGND_3") (pintype "input"))
      (node (ref "U16") (pin "9") (pinfunction "AGND_9") (pintype "input"))
      (node (ref "U17") (pin "4") (pinfunction "GND_4") (pintype "input"))
      (node (ref "U2") (pin "2") (pinfunction "GND_2") (pintype "unspecified"))
      (node (ref "U3") (pin "1") (pinfunction "A1_1") (pintype "unspecified"))
      (node (ref "U3") (pin "2") (pinfunction "A0_2") (pintype "unspecified"))
      (node (ref "U3") (pin "6") (pinfunction "GND_6") (pintype "unspecified"))
      (node (ref "U4") (pin "1") (pinfunction "K_1") (pintype "unspecified"))
      (node (ref "U5") (pin "1") (pinfunction "1_1") (pintype "unspecified"))
      (node (ref "U6") (pin "1") (pinfunction "1_1") (pintype "unspecified"))
      (node (ref "U7") (pin "4") (pinfunction "TD_4") (pintype "unspecified"))
      (node (ref "U8") (pin "13") (pinfunction "GND_13") (pintype "unspecified"))
      (node (ref "U9") (pin "21") (pinfunction "DRV_21") (pintype "unspecified"))
      (node (ref "U9") (pin "25") (pinfunction "VSS_25") (pintype "unspecified"))
      (node (ref "USB1") (pin "7") (pinfunction "EH_7") (pintype "unspecified"))
      (node (ref "USB1") (pin "A12") (pinfunction "GND_A12") (pintype "unspecified"))
      (node (ref "USB1") (pin "B12") (pinfunction "GND_B12") (pintype "unspecified"))
      (node (ref "USB2") (pin "4") (pinfunction "GND_4") (pintype "unspecified"))
      (node (ref "USB2") (pin "5") (pinfunction "GND_5") (pintype "unspecified"))
      (node (ref "USB2") (pin "6") (pinfunction "GND_6") (pintype "unspecified"))
      (node (ref "USB4") (pin "4") (pinfunction "GND_4") (pintype "unspecified"))
      (node (ref "USB4") (pin "5") (pinfunction "GND_5") (pintype "unspecified"))
      (node (ref "USB4") (pin "6") (pinfunction "GND_6") (pintype "unspecified"))
      (node (ref "USB5") (pin "0") (pinfunction "SH_0") (pintype "unspecified"))
      (node (ref "USB5") (pin "1") (pinfunction "SH_1") (pintype "unspecified"))
      (node (ref "USB5") (pin "2") (pinfunction "SH_2") (pintype "unspecified"))
      (node (ref "USB5") (pin "3") (pinfunction "SH_3") (pintype "unspecified"))
      (node (ref "USB5") (pin "A1") (pinfunction "GND_A1") (pintype "unspecified"))
      (node (ref "USB5") (pin "A12") (pinfunction "GND_A12") (pintype "unspecified"))
      (node (ref "USB5") (pin "B1") (pinfunction "GND_B1") (pintype "unspecified"))
      (node (ref "USB5") (pin "B12") (pinfunction "GND_B12") (pintype "unspecified"))
      (node (ref "X1") (pin "4") (pinfunction "VCC_4") (pintype "unspecified"))
    )
    (net (code "17") (name "GPIO02") (class "Default")
      (node (ref "H2") (pin "3") (pinfunction "3_3") (pintype "unspecified"))
      (node (ref "R8") (pin "2") (pinfunction "2_2") (pintype "input"))
      (node (ref "U18") (pin "3") (pinfunction "GPIO2/SDA1_3") (pintype "bidirectional"))
      (node (ref "U3") (pin "3") (pinfunction "SDA_3") (pintype "unspecified"))
      (node (ref "U8") (pin "15") (pinfunction "SDA_15") (pintype "bidirectional"))
    )
    (net (code "18") (name "GPIO03") (class "Default")
      (node (ref "H2") (pin "4") (pinfunction "4_4") (pintype "unspecified"))
      (node (ref "R7") (pin "1") (pinfunction "1_1") (pintype "input"))
      (node (ref "U18") (pin "5") (pinfunction "GPIO3/SCL_5") (pintype "bidirectional"))
      (node (ref "U3") (pin "4") (pinfunction "SCL_4") (pintype "unspecified"))
      (node (ref "U8") (pin "16") (pinfunction "SCL_16") (pintype "unspecified"))
    )
    (net (code "19") (name "GPIO17") (class "Default")
      (node (ref "H2") (pin "5") (pinfunction "5_5") (pintype "unspecified"))
      (node (ref "R10") (pin "1") (pinfunction "1_1") (pintype "input"))
      (node (ref "U18") (pin "11") (pinfunction "GPIO17/GPIO_GEN0_11") (pintype "bidirectional"))
    )
    (net (code "20") (name "GPIO18") (class "Default")
      (node (ref "H2") (pin "6") (pinfunction "6_6") (pintype "unspecified"))
      (node (ref "U16") (pin "13") (pinfunction "BCK_13") (pintype "input"))
      (node (ref "U18") (pin "12") (pinfunction "GPIO18/GPIO_GEN1_12") (pintype "bidirectional"))
    )
    (net (code "21") (name "GPIO19") (class "Default")
      (node (ref "H2") (pin "8") (pinfunction "8_8") (pintype "unspecified"))
      (node (ref "U16") (pin "15") (pinfunction "LRCK_15") (pintype "input"))
      (node (ref "U18") (pin "35") (pinfunction "GPIO19_35") (pintype "bidirectional"))
    )
    (net (code "22") (name "GPIO21") (class "Default")
      (node (ref "H2") (pin "7") (pinfunction "7_7") (pintype "unspecified"))
      (node (ref "U16") (pin "14") (pinfunction "DIN_14") (pintype "input"))
      (node (ref "U18") (pin "40") (pinfunction "GPIO21_40") (pintype "bidirectional"))
    )
    (net (code "23") (name "MDIN0") (class "Default")
      (node (ref "J1") (pin "6") (pinfunction "RD-_6") (pintype "unspecified"))
      (node (ref "U12") (pin "3") (pinfunction "MDIN0_3") (pintype "unspecified"))
    )
    (net (code "24") (name "MDIN1") (class "Default")
      (node (ref "J1") (pin "2") (pinfunction "TD-_2") (pintype "unspecified"))
      (node (ref "U12") (pin "5") (pinfunction "MDIN1_5") (pintype "unspecified"))
    )
    (net (code "25") (name "MDIP0") (class "Default")
      (node (ref "J1") (pin "1") (pinfunction "TD+_1") (pintype "unspecified"))
      (node (ref "U12") (pin "2") (pinfunction "MDIP0_2") (pintype "unspecified"))
    )
    (net (code "26") (name "MDIP1") (class "Default")
      (node (ref "J1") (pin "3") (pinfunction "RD+_3") (pintype "unspecified"))
      (node (ref "U12") (pin "4") (pinfunction "MDIP1_4") (pintype "unspecified"))
    )
    (net (code "27") (name "MOSFET_GATE") (class "Default")
      (node (ref "Q2") (pin "1") (pinfunction "G_1") (pintype "unspecified"))
      (node (ref "Q3") (pin "2") (pinfunction "COLLECTOR_2") (pintype "unspecified"))
      (node (ref "Q4") (pin "2") (pinfunction "COLLECTOR_2") (pintype "unspecified"))
      (node (ref "R9") (pin "1") (pinfunction "1_1") (pintype "unspecified"))
      (node (ref "SW2") (pin "4") (pinfunction "4_4") (pintype "unspecified"))
    )
    (net (code "28") (name "MOSFET_IN") (class "Default")
      (node (ref "Q2") (pin "2") (pinfunction "S_2") (pintype "unspecified"))
      (node (ref "U3") (pin "7") (pinfunction "IN–_7") (pintype "unspecified"))
    )
    (net (code "29") (name "Net-(C24-Pad1)") (class "Default")
      (node (ref "C24") (pin "1") (pinfunction "1_1") (pintype "unspecified"))
      (node (ref "U12") (pin "10") (pinfunction "AVDD33_10") (pintype "unspecified"))
    )
    (net (code "30") (name "Net-(C26-Pad1)") (class "Default")
      (node (ref "C26") (pin "1") (pinfunction "1_1") (pintype "unspecified"))
      (node (ref "U12") (pin "1") (pinfunction "AVDD33_1") (pintype "unspecified"))
    )
    (net (code "31") (name "Net-(C32-Pad1)") (class "Default")
      (node (ref "C32") (pin "1") (pinfunction "1_1") (pintype "input"))
      (node (ref "CN1") (pin "2") (pinfunction "2_2") (pintype "unspecified"))
    )
    (net (code "32") (name "Net-(C33-Pad1)") (class "Default")
      (node (ref "C33") (pin "1") (pinfunction "1_1") (pintype "input"))
      (node (ref "CN1") (pin "3") (pinfunction "3_3") (pintype "unspecified"))
    )
    (net (code "33") (name "Net-(D1-A)") (class "Default")
      (node (ref "D1") (pin "2") (pinfunction "A_2") (pintype "unspecified"))
      (node (ref "L2") (pin "2") (pinfunction "2_2") (pintype "input"))
      (node (ref "U2") (pin "1") (pinfunction "SW_1") (pintype "unspecified"))
    )
    (net (code "34") (name "Net-(J1-CHS_GND)") (class "Default")
      (node (ref "C15") (pin "1") (pinfunction "1_1") (pintype "unspecified"))
      (node (ref "J1") (pin "8") (pinfunction "CHS_GND_8") (pintype "unspecified"))
    )
    (net (code "35") (name "Net-(J1-Pad9)") (class "Default")
      (node (ref "J1") (pin "9") (pinfunction "9_9") (pintype "unspecified"))
      (node (ref "R21") (pin "1") (pinfunction "1_1") (pintype "input"))
    )
    (net (code "36") (name "Net-(J1-Pad12)") (class "Default")
      (node (ref "J1") (pin "12") (pinfunction "12_12") (pintype "unspecified"))
      (node (ref "R22") (pin "1") (pinfunction "1_1") (pintype "input"))
    )
    (net (code "37") (name "Net-(Q1-G1)") (class "Default")
      (node (ref "Q1") (pin "6") (pinfunction "G1_6") (pintype "unspecified"))
      (node (ref "U7") (pin "1") (pinfunction "OD_1") (pintype "unspecified"))
    )
    (net (code "38") (name "Net-(Q1-G2)") (class "Default")
      (node (ref "Q1") (pin "4") (pinfunction "G2_4") (pintype "unspecified"))
      (node (ref "U7") (pin "3") (pinfunction "OC_3") (pintype "unspecified"))
    )
    (net (code "39") (name "Net-(Q3-BASE)") (class "Default")
      (node (ref "Q3") (pin "1") (pinfunction "BASE_1") (pintype "unspecified"))
      (node (ref "R10") (pin "2") (pinfunction "2_2") (pintype "input"))
      (node (ref "R11") (pin "2") (pinfunction "2_2") (pintype "input"))
    )
    (net (code "40") (name "Net-(Q4-BASE)") (class "Default")
      (node (ref "Q4") (pin "1") (pinfunction "BASE_1") (pintype "unspecified"))
      (node (ref "R13") (pin "2") (pinfunction "2_2") (pintype "input"))
    )
    (net (code "41") (name "Net-(R19-Pad1)") (class "Default")
      (node (ref "R19") (pin "1") (pinfunction "1_1") (pintype "input"))
      (node (ref "U14") (pin "1") (pinfunction "1_1") (pintype "unspecified"))
    )
    (net (code "42") (name "Net-(U1-ISET)") (class "Default")
      (node (ref "R2") (pin "2") (pinfunction "2_2") (pintype "unspecified"))
      (node (ref "U1") (pin "5") (pinfunction "ISET_5") (pintype "unspecified"))
    )
    (net (code "43") (name "Net-(U1-NTC)") (class "Default")
      (node (ref "R1") (pin "2") (pinfunction "2_2") (pintype "input"))
      (node (ref "U1") (pin "3") (pinfunction "NTC_3") (pintype "unspecified"))
    )
    (net (code "44") (name "Net-(U1-STAT)") (class "Default")
      (node (ref "R3") (pin "2") (pinfunction "2_2") (pintype "input"))
      (node (ref "U1") (pin "4") (pinfunction "STAT_4") (pintype "unspecified"))
    )
    (net (code "45") (name "Net-(U1-SW)") (class "Default")
      (node (ref "L1") (pin "2") (pinfunction "2_2") (pintype "unspecified"))
      (node (ref "U1") (pin "1") (pinfunction "SW_1") (pintype "unspecified"))
    )
    (net (code "46") (name "Net-(U2-FB)") (class "Default")
      (node (ref "R5") (pin "1") (pinfunction "1_1") (pintype "unspecified"))
      (node (ref "R6") (pin "2") (pinfunction "2_2") (pintype "unspecified"))
      (node (ref "U2") (pin "3") (pinfunction "FB_3") (pintype "unspecified"))
    )
    (net (code "47") (name "Net-(U4-A)") (class "Default")
      (node (ref "R3") (pin "1") (pinfunction "1_1") (pintype "input"))
      (node (ref "U4") (pin "2") (pinfunction "A_2") (pintype "unspecified"))
    )
    (net (code "48") (name "Net-(U7-VM)") (class "Default")
      (node (ref "Q1") (pin "5") (pinfunction "D1/D2_5") (pintype "unspecified"))
      (node (ref "U7") (pin "2") (pinfunction "VM_2") (pintype "unspecified"))
    )
    (net (code "49") (name "Net-(U8A-INTSQW)") (class "Default")
      (node (ref "R12") (pin "2") (pinfunction "2_2") (pintype "input"))
      (node (ref "R13") (pin "1") (pinfunction "1_1") (pintype "input"))
      (node (ref "U8") (pin "3") (pinfunction "INTSQW_3") (pintype "unspecified"))
    )
    (net (code "50") (name "Net-(U8A-VBAT)") (class "Default")
      (node (ref "BAT1") (pin "2") (pinfunction "2_2") (pintype "input"))
      (node (ref "U8") (pin "14") (pinfunction "VBAT_14") (pintype "unspecified"))
    )
    (net (code "51") (name "Net-(U9-LED2)") (class "Default")
      (node (ref "U14") (pin "2") (pinfunction "2_2") (pintype "unspecified"))
      (node (ref "U9") (pin "23") (pinfunction "LED2_23") (pintype "unspecified"))
    )
    (net (code "52") (name "Net-(U9-OVCJ)") (class "Default")
      (node (ref "R18") (pin "2") (pinfunction "2_2") (pintype "input"))
      (node (ref "U9") (pin "1") (pinfunction "OVCJ_1") (pintype "unspecified"))
    )
    (net (code "53") (name "Net-(U9-REXT)") (class "Default")
      (node (ref "R17") (pin "1") (pinfunction "1_1") (pintype "unspecified"))
      (node (ref "U9") (pin "13") (pinfunction "REXT_13") (pintype "unspecified"))
    )
    (net (code "54") (name "Net-(U9-XRSTJ)") (class "Default")
      (node (ref "R16") (pin "2") (pinfunction "2_2") (pintype "input"))
      (node (ref "U9") (pin "16") (pinfunction "XRSTJ_16") (pintype "unspecified"))
    )
    (net (code "55") (name "Net-(U12-AVDD10)") (class "Default")
      (node (ref "C19") (pin "2") (pinfunction "2_2") (pintype "input"))
      (node (ref "U12") (pin "23") (pinfunction "AVDD10_23") (pintype "unspecified"))
    )
    (net (code "56") (name "Net-(U12-DVDD10)") (class "Default")
      (node (ref "C20") (pin "2") (pinfunction "2_2") (pintype "input"))
      (node (ref "U12") (pin "16") (pinfunction "DVDD10_16") (pintype "unspecified"))
    )
    (net (code "57") (name "Net-(U12-DVDD33)") (class "Default")
      (node (ref "C25") (pin "2") (pinfunction "2_2") (pintype "unspecified"))
      (node (ref "U12") (pin "13") (pinfunction "DVDD33_13") (pintype "unspecified"))
    )
    (net (code "58") (name "Net-(U12-LED1{slash}SPISCK)") (class "Default")
      (node (ref "R20") (pin "2") (pinfunction "2_2") (pintype "input"))
      (node (ref "U12") (pin "17") (pinfunction "LED1/SPISCK_17") (pintype "unspecified"))
    )
    (net (code "59") (name "Net-(U12-RSET)") (class "Default")
      (node (ref "R23") (pin "1") (pinfunction "1_1") (pintype "input"))
      (node (ref "U12") (pin "24") (pinfunction "RSET_24") (pintype "unspecified"))
    )
    (net (code "60") (name "Net-(U12-U2DM)") (class "Default")
      (node (ref "R24") (pin "1") (pinfunction "1_1") (pintype "unspecified"))
      (node (ref "U12") (pin "7") (pinfunction "U2DM_7") (pintype "unspecified"))
    )
    (net (code "61") (name "Net-(U12-U2DP)") (class "Default")
      (node (ref "R25") (pin "1") (pinfunction "1_1") (pintype "unspecified"))
      (node (ref "U12") (pin "8") (pinfunction "U2DP_8") (pintype "unspecified"))
    )
    (net (code "62") (name "Net-(U12-U2VDD10)") (class "Default")
      (node (ref "C14") (pin "2") (pinfunction "2_2") (pintype "input"))
      (node (ref "U12") (pin "9") (pinfunction "U2VDD10_9") (pintype "unspecified"))
    )
    (net (code "63") (name "Net-(U15-A)") (class "Default")
      (node (ref "R20") (pin "1") (pinfunction "1_1") (pintype "input"))
      (node (ref "U15") (pin "2") (pinfunction "A_2") (pintype "unspecified"))
    )
    (net (code "64") (name "Net-(U16-CAPM)") (class "Default")
      (node (ref "C36") (pin "1") (pinfunction "1_1") (pintype "input"))
      (node (ref "U16") (pin "4") (pinfunction "CAPM_4") (pintype "input"))
    )
    (net (code "65") (name "Net-(U16-CAPP)") (class "Default")
      (node (ref "C36") (pin "2") (pinfunction "2_2") (pintype "input"))
      (node (ref "U16") (pin "2") (pinfunction "CAPP_2") (pintype "input"))
    )
    (net (code "66") (name "Net-(U16-CPVDD)") (class "Default")
      (node (ref "C29") (pin "1") (pinfunction "1_1") (pintype "input"))
      (node (ref "U16") (pin "1") (pinfunction "CPVDD_1") (pintype "input"))
    )
    (net (code "67") (name "Net-(U16-DVDD)") (class "Default")
      (node (ref "C28") (pin "1") (pinfunction "1_1") (pintype "unspecified"))
      (node (ref "U16") (pin "20") (pinfunction "DVDD_20") (pintype "input"))
    )
    (net (code "68") (name "Net-(U16-FLT)") (class "Default")
      (node (ref "C31") (pin "1") (pinfunction "1_1") (pintype "input"))
      (node (ref "U16") (pin "11") (pinfunction "FLT_11") (pintype "input"))
    )
    (net (code "69") (name "Net-(U16-OUTL)") (class "Default")
      (node (ref "C32") (pin "2") (pinfunction "2_2") (pintype "input"))
      (node (ref "U16") (pin "6") (pinfunction "OUTL_6") (pintype "input"))
    )
    (net (code "70") (name "Net-(U16-OUTR)") (class "Default")
      (node (ref "C33") (pin "2") (pinfunction "2_2") (pintype "input"))
      (node (ref "U16") (pin "7") (pinfunction "OUTR_7") (pintype "input"))
    )
    (net (code "71") (name "Net-(USB1-CC1)") (class "Default")
      (node (ref "U5") (pin "2") (pinfunction "2_2") (pintype "unspecified"))
      (node (ref "USB1") (pin "A5") (pinfunction "CC1_A5") (pintype "unspecified"))
    )
    (net (code "72") (name "Net-(USB1-CC2)") (class "Default")
      (node (ref "U6") (pin "2") (pinfunction "2_2") (pintype "unspecified"))
      (node (ref "USB1") (pin "B5") (pinfunction "CC2_B5") (pintype "unspecified"))
    )
    (net (code "73") (name "Net-(USB5-CC1)") (class "Default")
      (node (ref "U11") (pin "1") (pinfunction "1_1") (pintype "unspecified"))
      (node (ref "USB5") (pin "A5") (pinfunction "CC1_A5") (pintype "unspecified"))
    )
    (net (code "74") (name "Net-(USB5-CC2)") (class "Default")
      (node (ref "U10") (pin "2") (pinfunction "2_2") (pintype "unspecified"))
      (node (ref "USB5") (pin "B5") (pinfunction "CC2_B5") (pintype "unspecified"))
    )
    (net (code "75") (name "PGND") (class "Default")
      (node (ref "U1") (pin "2") (pinfunction "PGND_2") (pintype "unspecified"))
    )
    (net (code "76") (name "PI_3V3") (class "Default")
      (node (ref "C24") (pin "2") (pinfunction "2_2") (pintype "unspecified"))
      (node (ref "C25") (pin "1") (pinfunction "1_1") (pintype "unspecified"))
      (node (ref "C26") (pin "2") (pinfunction "2_2") (pintype "unspecified"))
      (node (ref "C27") (pin "2") (pinfunction "2_2") (pintype "unspecified"))
      (node (ref "C28") (pin "2") (pinfunction "2_2") (pintype "unspecified"))
      (node (ref "C29") (pin "2") (pinfunction "2_2") (pintype "input"))
      (node (ref "C30") (pin "1") (pinfunction "1_1") (pintype "unspecified"))
      (node (ref "R12") (pin "1") (pinfunction "1_1") (pintype "input"))
      (node (ref "R16") (pin "1") (pinfunction "1_1") (pintype "input"))
      (node (ref "R18") (pin "1") (pinfunction "1_1") (pintype "input"))
      (node (ref "R21") (pin "2") (pinfunction "2_2") (pintype "input"))
      (node (ref "R22") (pin "2") (pinfunction "2_2") (pintype "input"))
      (node (ref "R23") (pin "2") (pinfunction "2_2") (pintype "input"))
      (node (ref "R7") (pin "2") (pinfunction "2_2") (pintype "input"))
      (node (ref "R8") (pin "1") (pinfunction "1_1") (pintype "input"))
      (node (ref "U16") (pin "17") (pinfunction "XSMT_17") (pintype "input"))
      (node (ref "U3") (pin "5") (pinfunction "VS_5") (pintype "unspecified"))
    )
    (net (code "77") (name "PI_5V") (class "Default")
      (node (ref "C5") (pin "2") (pinfunction "2_2") (pintype "unspecified"))
      (node (ref "C6") (pin "1") (pinfunction "1_1") (pintype "unspecified"))
      (node (ref "C8") (pin "2") (pinfunction "2_2") (pintype "unspecified"))
      (node (ref "C9") (pin "1") (pinfunction "1_1") (pintype "input"))
      (node (ref "H2") (pin "2") (pinfunction "2_2") (pintype "unspecified"))
      (node (ref "Q2") (pin "3") (pinfunction "D_3") (pintype "unspecified"))
    )
    (net (code "78") (name "PI_USB_D+") (class "Default")
      (node (ref "R15") (pin "2") (pinfunction "2_2") (pintype "unspecified"))
      (node (ref "U9") (pin "15") (pinfunction "DPU_15") (pintype "unspecified"))
    )
    (net (code "79") (name "PI_USB_D-") (class "Default")
      (node (ref "R14") (pin "2") (pinfunction "2_2") (pintype "unspecified"))
      (node (ref "U9") (pin "14") (pinfunction "DMU_14") (pintype "unspecified"))
    )
    (net (code "80") (name "SYS") (class "Default")
      (node (ref "C3") (pin "1") (pinfunction "1_1") (pintype "unspecified"))
      (node (ref "L1") (pin "1") (pinfunction "1_1") (pintype "unspecified"))
      (node (ref "L2") (pin "1") (pinfunction "1_1") (pintype "input"))
      (node (ref "U1") (pin "7") (pinfunction "SYS_7") (pintype "unspecified"))
      (node (ref "U2") (pin "4") (pinfunction "EN_4") (pintype "unspecified"))
      (node (ref "U2") (pin "5") (pinfunction "IN_5") (pintype "unspecified"))
    )
    (net (code "81") (name "USBDM") (class "Default")
      (node (ref "H1") (pin "1") (pinfunction "1_1") (pintype "unspecified"))
      (node (ref "R14") (pin "1") (pinfunction "1_1") (pintype "unspecified"))
      (node (ref "U18") (pin "42") (pinfunction "USBDM_42") (pintype "bidirectional"))
    )
    (net (code "82") (name "USBDP") (class "Default")
      (node (ref "H1") (pin "2") (pinfunction "2_2") (pintype "unspecified"))
      (node (ref "R15") (pin "1") (pinfunction "1_1") (pintype "unspecified"))
      (node (ref "U18") (pin "41") (pinfunction "USBDP_41") (pintype "bidirectional"))
    )
    (net (code "83") (name "VD33F") (class "Default")
      (node (ref "C10") (pin "2") (pinfunction "2_2") (pintype "unspecified"))
      (node (ref "C11") (pin "1") (pinfunction "1_1") (pintype "unspecified"))
      (node (ref "U9") (pin "20") (pinfunction "VD33F_20") (pintype "unspecified"))
    )
    (net (code "84") (name "XIN") (class "Default")
      (node (ref "C12") (pin "2") (pinfunction "2_2") (pintype "unspecified"))
      (node (ref "U9") (pin "4") (pinfunction "XIN_4") (pintype "unspecified"))
      (node (ref "X1") (pin "1") (pinfunction "tri_1") (pintype "unspecified"))
    )
    (net (code "85") (name "XO") (class "Default")
      (node (ref "C13") (pin "2") (pinfunction "2_2") (pintype "unspecified"))
      (node (ref "U9") (pin "3") (pinfunction "XOUT_3") (pintype "unspecified"))
      (node (ref "X1") (pin "3") (pinfunction "OUT_3") (pintype "unspecified"))
    )
    (net (code "86") (name "unconnected-(C18-Pad2)") (class "Default")
      (node (ref "C18") (pin "2") (pinfunction "2_2") (pintype "input"))
    )
    (net (code "87") (name "unconnected-(C21-Pad1)") (class "Default")
      (node (ref "C21") (pin "1") (pinfunction "1_1") (pintype "input"))
    )
    (net (code "88") (name "unconnected-(C21-Pad2)") (class "Default")
      (node (ref "C21") (pin "2") (pinfunction "2_2") (pintype "input"))
    )
    (net (code "89") (name "unconnected-(CN1-Pad4)") (class "Default")
      (node (ref "CN1") (pin "4") (pinfunction "4_4") (pintype "unspecified+no_connect"))
    )
    (net (code "90") (name "unconnected-(CN1-Pad6)") (class "Default")
      (node (ref "CN1") (pin "6") (pinfunction "6_6") (pintype "unspecified+no_connect"))
    )
    (net (code "91") (name "unconnected-(J1-NC-Pad7)") (class "Default")
      (node (ref "J1") (pin "7") (pinfunction "NC_7") (pintype "unspecified+no_connect"))
    )
    (net (code "92") (name "unconnected-(J1-Pad4)") (class "Default")
      (node (ref "J1") (pin "4") (pinfunction "4_4") (pintype "unspecified"))
    )
    (net (code "93") (name "unconnected-(J1-Pad5)") (class "Default")
      (node (ref "J1") (pin "5") (pinfunction "5_5") (pintype "unspecified"))
    )
    (net (code "94") (name "unconnected-(J1-PadSH2)") (class "Default")
      (node (ref "J1") (pin "SH2") (pinfunction "SH2_SH2") (pintype "unspecified"))
    )
    (net (code "95") (name "unconnected-(Q1-D1{slash}D2-Pad2)") (class "Default")
      (node (ref "Q1") (pin "2") (pinfunction "D1/D2_2") (pintype "unspecified"))
    )
    (net (code "96") (name "unconnected-(SW2-Pad2)") (class "Default")
      (node (ref "SW2") (pin "2") (pinfunction "2_2") (pintype "unspecified"))
    )
    (net (code "97") (name "unconnected-(SW2-Pad3)") (class "Default")
      (node (ref "SW2") (pin "3") (pinfunction "3_3") (pintype "unspecified"))
    )
    (net (code "98") (name "unconnected-(U2-NC-Pad6)") (class "Default")
      (node (ref "U2") (pin "6") (pinfunction "NC_6") (pintype "unspecified+no_connect"))
    )
    (net (code "99") (name "unconnected-(U8A-32kHz-Pad1)") (class "Default")
      (node (ref "U8") (pin "1") (pinfunction "32kHz_1") (pintype "unspecified+no_connect"))
    )
    (net (code "100") (name "unconnected-(U8A-RST-Pad4)") (class "Default")
      (node (ref "U8") (pin "4") (pinfunction "RST_4") (pintype "bidirectional+no_connect"))
    )
    (net (code "101") (name "unconnected-(U8A-VCC-Pad2)") (class "Default")
      (node (ref "U8") (pin "2") (pinfunction "VCC_2") (pintype "unspecified"))
    )
    (net (code "102") (name "unconnected-(U9-LED1-Pad22)") (class "Default")
      (node (ref "U9") (pin "22") (pinfunction "LED1_22") (pintype "unspecified+no_connect"))
    )
    (net (code "103") (name "unconnected-(U9-PWRJ-Pad24)") (class "Default")
      (node (ref "U9") (pin "24") (pinfunction "PWRJ_24") (pintype "unspecified+no_connect"))
    )
    (net (code "104") (name "unconnected-(U9-TESTJ-Pad2)") (class "Default")
      (node (ref "U9") (pin "2") (pinfunction "TESTJ_2") (pintype "unspecified+no_connect"))
    )
    (net (code "105") (name "unconnected-(U12-DVDD10_UPS-Pad12)") (class "Default")
      (node (ref "U12") (pin "12") (pinfunction "DVDD10_UPS_12") (pintype "unspecified"))
    )
    (net (code "106") (name "unconnected-(U12-GPIO-Pad14)") (class "Default")
      (node (ref "U12") (pin "14") (pinfunction "GPIO_14") (pintype "unspecified+no_connect"))
    )
    (net (code "107") (name "unconnected-(U12-LANWAKEB-Pad19)") (class "Default")
      (node (ref "U12") (pin "19") (pinfunction "LANWAKEB_19") (pintype "unspecified+no_connect"))
    )
    (net (code "108") (name "unconnected-(U12-LED0{slash}SPICSB-Pad15)") (class "Default")
      (node (ref "U12") (pin "15") (pinfunction "LED0/SPICSB_15") (pintype "unspecified+no_connect"))
    )
    (net (code "109") (name "unconnected-(U12-SPISDI{slash}XTALDET-Pad18)") (class "Default")
      (node (ref "U12") (pin "18") (pinfunction "SPISDI/XTALDET_18") (pintype "unspecified+no_connect"))
    )
    (net (code "110") (name "unconnected-(U12-SPISDO-Pad20)") (class "Default")
      (node (ref "U12") (pin "20") (pinfunction "SPISDO_20") (pintype "unspecified+no_connect"))
    )
    (net (code "111") (name "unconnected-(U16-LDOO-Pad18)") (class "Default")
      (node (ref "U16") (pin "18") (pinfunction "LDOO_18") (pintype "input+no_connect"))
    )
    (net (code "112") (name "unconnected-(U16-VNEG-Pad5)") (class "Default")
      (node (ref "U16") (pin "5") (pinfunction "VNEG_5") (pintype "input+no_connect"))
    )
    (net (code "113") (name "unconnected-(U17-GND-Pad2)") (class "Default")
      (node (ref "U17") (pin "2") (pinfunction "GND_2") (pintype "input"))
    )
    (net (code "114") (name "unconnected-(U18-3V3_1-Pad1)") (class "Default")
      (node (ref "U18") (pin "1") (pinfunction "3V3_1_1") (pintype "unspecified"))
    )
    (net (code "115") (name "unconnected-(U18-3V3_17-Pad17)") (class "Default")
      (node (ref "U18") (pin "17") (pinfunction "3V3_17_17") (pintype "unspecified"))
    )
    (net (code "116") (name "unconnected-(U18-5V_2-Pad2)") (class "Default")
      (node (ref "U18") (pin "2") (pinfunction "5V_2_2") (pintype "unspecified"))
    )
    (net (code "117") (name "unconnected-(U18-5V_4-Pad4)") (class "Default")
      (node (ref "U18") (pin "4") (pinfunction "5V_4_4") (pintype "unspecified"))
    )
    (net (code "118") (name "unconnected-(U18-GND_6-Pad6)") (class "Default")
      (node (ref "U18") (pin "6") (pinfunction "GND_6_6") (pintype "unspecified"))
    )
    (net (code "119") (name "unconnected-(U18-GND_9-Pad9)") (class "Default")
      (node (ref "U18") (pin "9") (pinfunction "GND_9_9") (pintype "unspecified"))
    )
    (net (code "120") (name "unconnected-(U18-GND_14-Pad14)") (class "Default")
      (node (ref "U18") (pin "14") (pinfunction "GND_14_14") (pintype "unspecified"))
    )
    (net (code "121") (name "unconnected-(U18-GND_20-Pad20)") (class "Default")
      (node (ref "U18") (pin "20") (pinfunction "GND_20_20") (pintype "unspecified"))
    )
    (net (code "122") (name "unconnected-(U18-GND_25-Pad25)") (class "Default")
      (node (ref "U18") (pin "25") (pinfunction "GND_25_25") (pintype "unspecified"))
    )
    (net (code "123") (name "unconnected-(U18-GND_30-Pad30)") (class "Default")
      (node (ref "U18") (pin "30") (pinfunction "GND_30_30") (pintype "unspecified"))
    )
    (net (code "124") (name "unconnected-(U18-GND_34-Pad34)") (class "Default")
      (node (ref "U18") (pin "34") (pinfunction "GND_34_34") (pintype "unspecified"))
    )
    (net (code "125") (name "unconnected-(U18-GND_39-Pad39)") (class "Default")
      (node (ref "U18") (pin "39") (pinfunction "GND_39_39") (pintype "unspecified"))
    )
    (net (code "126") (name "unconnected-(U18-GPIO4{slash}GPIO_GCLK-Pad7)") (class "Default")
      (node (ref "U18") (pin "7") (pinfunction "GPIO4/GPIO_GCLK_7") (pintype "bidirectional"))
    )
    (net (code "127") (name "unconnected-(U18-GPIO5-Pad29)") (class "Default")
      (node (ref "U18") (pin "29") (pinfunction "GPIO5_29") (pintype "bidirectional"))
    )
    (net (code "128") (name "unconnected-(U18-GPIO6-Pad31)") (class "Default")
      (node (ref "U18") (pin "31") (pinfunction "GPIO6_31") (pintype "bidirectional"))
    )
    (net (code "129") (name "unconnected-(U18-GPIO7{slash}SPI_~CE1~-Pad26)") (class "Default")
      (node (ref "U18") (pin "26") (pinfunction "GPIO7/SPI_~CE1~_26") (pintype "bidirectional"))
    )
    (net (code "130") (name "unconnected-(U18-GPIO8{slash}SPI_~CE0~-Pad24)") (class "Default")
      (node (ref "U18") (pin "24") (pinfunction "GPIO8/SPI_~CE0~_24") (pintype "bidirectional"))
    )
    (net (code "131") (name "unconnected-(U18-GPIO9{slash}SPI_MISO-Pad21)") (class "Default")
      (node (ref "U18") (pin "21") (pinfunction "GPIO9/SPI_MISO_21") (pintype "bidirectional"))
    )
    (net (code "132") (name "unconnected-(U18-GPIO10{slash}SPI_MOSI-Pad19)") (class "Default")
      (node (ref "U18") (pin "19") (pinfunction "GPIO10/SPI_MOSI_19") (pintype "bidirectional"))
    )
    (net (code "133") (name "unconnected-(U18-GPIO11{slash}SPI_SCLK-Pad23)") (class "Default")
      (node (ref "U18") (pin "23") (pinfunction "GPIO11/SPI_SCLK_23") (pintype "bidirectional"))
    )
    (net (code "134") (name "unconnected-(U18-GPIO12-Pad32)") (class "Default")
      (node (ref "U18") (pin "32") (pinfunction "GPIO12_32") (pintype "bidirectional"))
    )
    (net (code "135") (name "unconnected-(U18-GPIO13-Pad33)") (class "Default")
      (node (ref "U18") (pin "33") (pinfunction "GPIO13_33") (pintype "bidirectional"))
    )
    (net (code "136") (name "unconnected-(U18-GPIO14{slash}TXD0-Pad8)") (class "Default")
      (node (ref "U18") (pin "8") (pinfunction "GPIO14/TXD0_8") (pintype "bidirectional"))
    )
    (net (code "137") (name "unconnected-(U18-GPIO15{slash}RXD0-Pad10)") (class "Default")
      (node (ref "U18") (pin "10") (pinfunction "GPIO15/RXD0_10") (pintype "bidirectional"))
    )
    (net (code "138") (name "unconnected-(U18-GPIO16-Pad36)") (class "Default")
      (node (ref "U18") (pin "36") (pinfunction "GPIO16_36") (pintype "bidirectional"))
    )
    (net (code "139") (name "unconnected-(U18-GPIO20-Pad38)") (class "Default")
      (node (ref "U18") (pin "38") (pinfunction "GPIO20_38") (pintype "bidirectional"))
    )
    (net (code "140") (name "unconnected-(U18-GPIO22{slash}GPIO_GEN3-Pad15)") (class "Default")
      (node (ref "U18") (pin "15") (pinfunction "GPIO22/GPIO_GEN3_15") (pintype "bidirectional"))
    )
    (net (code "141") (name "unconnected-(U18-GPIO23{slash}GPIO_GEN4-Pad16)") (class "Default")
      (node (ref "U18") (pin "16") (pinfunction "GPIO23/GPIO_GEN4_16") (pintype "bidirectional"))
    )
    (net (code "142") (name "unconnected-(U18-GPIO24{slash}GPIO_GEN5-Pad18)") (class "Default")
      (node (ref "U18") (pin "18") (pinfunction "GPIO24/GPIO_GEN5_18") (pintype "bidirectional"))
    )
    (net (code "143") (name "unconnected-(U18-GPIO25{slash}GPIO_GEN6-Pad22)") (class "Default")
      (node (ref "U18") (pin "22") (pinfunction "GPIO25/GPIO_GEN6_22") (pintype "bidirectional"))
    )
    (net (code "144") (name "unconnected-(U18-GPIO26-Pad37)") (class "Default")
      (node (ref "U18") (pin "37") (pinfunction "GPIO26_37") (pintype "bidirectional"))
    )
    (net (code "145") (name "unconnected-(U18-GPIO27{slash}GPIO_GEN2-Pad13)") (class "Default")
      (node (ref "U18") (pin "13") (pinfunction "GPIO27/GPIO_GEN2_13") (pintype "bidirectional"))
    )
    (net (code "146") (name "unconnected-(U18-ID_SC-Pad28)") (class "Default")
      (node (ref "U18") (pin "28") (pinfunction "ID_SC_28") (pintype "bidirectional"))
    )
    (net (code "147") (name "unconnected-(U18-ID_SD-Pad27)") (class "Default")
      (node (ref "U18") (pin "27") (pinfunction "ID_SD_27") (pintype "bidirectional"))
    )
    (net (code "148") (name "unconnected-(USB5-SBU1-PadA8)") (class "Default")
      (node (ref "USB5") (pin "A8") (pinfunction "SBU1_A8") (pintype "unspecified+no_connect"))
    )
    (net (code "149") (name "unconnected-(USB5-SBU2-PadB8)") (class "Default")
      (node (ref "USB5") (pin "B8") (pinfunction "SBU2_B8") (pintype "unspecified+no_connect"))
    )
    (net (code "150") (name "unconnected-(X1-GND-Pad2)") (class "Default")
      (node (ref "X1") (pin "2") (pinfunction "GND_2") (pintype "unspecified"))
    )
  )
)
